# charlie.net
KiCad netlist of a schematic drawn in EAGLE
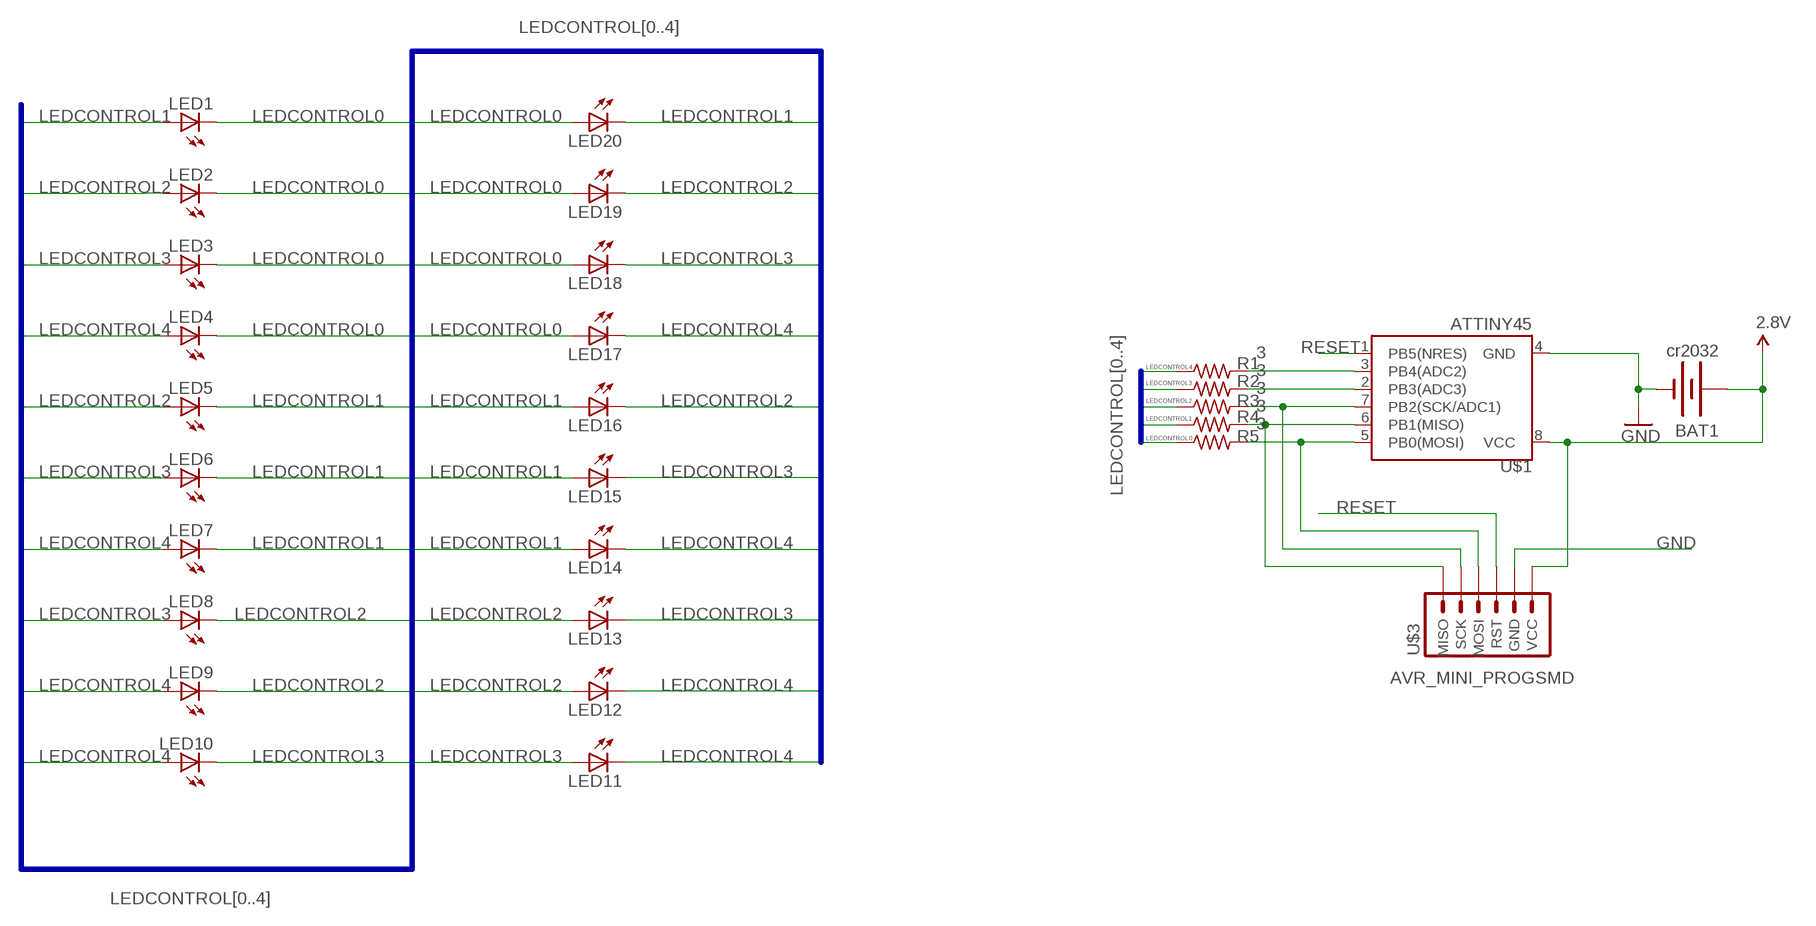
[diagram p0: schematic, sheet 1]

(export (version "E")
  (design (tool "Eeschema 10.0.6"))
  (components
    (comp (ref "BAT1")
      (value "cr2032")
      (footprint "eagle-import:BATTCON_20MM")
      (libsource (lib "eagle-import") (part "BATTERY20SMD"))
    )
    (comp (ref "LED1")
      (value "LEDCHIP-LED0805")
      (footprint "eagle-import:CHIP-LED0805")
      (libsource (lib "eagle-import") (part "LEDCHIP-LED0805"))
    )
    (comp (ref "LED2")
      (value "LEDCHIP-LED0805")
      (footprint "eagle-import:CHIP-LED0805")
      (libsource (lib "eagle-import") (part "LEDCHIP-LED0805"))
    )
    (comp (ref "LED3")
      (value "LEDCHIP-LED0805")
      (footprint "eagle-import:CHIP-LED0805")
      (libsource (lib "eagle-import") (part "LEDCHIP-LED0805"))
    )
    (comp (ref "LED4")
      (value "LEDCHIP-LED0805")
      (footprint "eagle-import:CHIP-LED0805")
      (libsource (lib "eagle-import") (part "LEDCHIP-LED0805"))
    )
    (comp (ref "LED5")
      (value "LEDCHIP-LED0805")
      (footprint "eagle-import:CHIP-LED0805")
      (libsource (lib "eagle-import") (part "LEDCHIP-LED0805"))
    )
    (comp (ref "LED6")
      (value "LEDCHIP-LED0805")
      (footprint "eagle-import:CHIP-LED0805")
      (libsource (lib "eagle-import") (part "LEDCHIP-LED0805"))
    )
    (comp (ref "LED7")
      (value "LEDCHIP-LED0805")
      (footprint "eagle-import:CHIP-LED0805")
      (libsource (lib "eagle-import") (part "LEDCHIP-LED0805"))
    )
    (comp (ref "LED8")
      (value "LEDCHIP-LED0805")
      (footprint "eagle-import:CHIP-LED0805")
      (libsource (lib "eagle-import") (part "LEDCHIP-LED0805"))
    )
    (comp (ref "LED9")
      (value "LEDCHIP-LED0805")
      (footprint "eagle-import:CHIP-LED0805")
      (libsource (lib "eagle-import") (part "LEDCHIP-LED0805"))
    )
    (comp (ref "LED10")
      (value "LEDCHIP-LED0805")
      (footprint "eagle-import:CHIP-LED0805")
      (libsource (lib "eagle-import") (part "LEDCHIP-LED0805"))
    )
    (comp (ref "LED11")
      (value "LEDCHIP-LED0805")
      (footprint "eagle-import:CHIP-LED0805")
      (libsource (lib "eagle-import") (part "LEDCHIP-LED0805"))
    )
    (comp (ref "LED12")
      (value "LEDCHIP-LED0805")
      (footprint "eagle-import:CHIP-LED0805")
      (libsource (lib "eagle-import") (part "LEDCHIP-LED0805"))
    )
    (comp (ref "LED13")
      (value "LEDCHIP-LED0805")
      (footprint "eagle-import:CHIP-LED0805")
      (libsource (lib "eagle-import") (part "LEDCHIP-LED0805"))
    )
    (comp (ref "LED14")
      (value "LEDCHIP-LED0805")
      (footprint "eagle-import:CHIP-LED0805")
      (libsource (lib "eagle-import") (part "LEDCHIP-LED0805"))
    )
    (comp (ref "LED15")
      (value "LEDCHIP-LED0805")
      (footprint "eagle-import:CHIP-LED0805")
      (libsource (lib "eagle-import") (part "LEDCHIP-LED0805"))
    )
    (comp (ref "LED16")
      (value "LEDCHIP-LED0805")
      (footprint "eagle-import:CHIP-LED0805")
      (libsource (lib "eagle-import") (part "LEDCHIP-LED0805"))
    )
    (comp (ref "LED17")
      (value "LEDCHIP-LED0805")
      (footprint "eagle-import:CHIP-LED0805")
      (libsource (lib "eagle-import") (part "LEDCHIP-LED0805"))
    )
    (comp (ref "LED18")
      (value "LEDCHIP-LED0805")
      (footprint "eagle-import:CHIP-LED0805")
      (libsource (lib "eagle-import") (part "LEDCHIP-LED0805"))
    )
    (comp (ref "LED19")
      (value "LEDCHIP-LED0805")
      (footprint "eagle-import:CHIP-LED0805")
      (libsource (lib "eagle-import") (part "LEDCHIP-LED0805"))
    )
    (comp (ref "LED20")
      (value "LEDCHIP-LED0805")
      (footprint "eagle-import:CHIP-LED0805")
      (libsource (lib "eagle-import") (part "LEDCHIP-LED0805"))
    )
    (comp (ref "R1")
      (value "3")
      (footprint "eagle-import:R0805")
      (libsource (lib "eagle-import") (part "R-US_R0805"))
    )
    (comp (ref "R2")
      (value "3")
      (footprint "eagle-import:R0805")
      (libsource (lib "eagle-import") (part "R-US_R0805"))
    )
    (comp (ref "R3")
      (value "3")
      (footprint "eagle-import:R0805")
      (libsource (lib "eagle-import") (part "R-US_R0805"))
    )
    (comp (ref "R4")
      (value "3")
      (footprint "eagle-import:R0805")
      (libsource (lib "eagle-import") (part "R-US_R0805"))
    )
    (comp (ref "R5")
      (value "3")
      (footprint "eagle-import:R0805")
      (libsource (lib "eagle-import") (part "R-US_R0805"))
    )
    (comp (ref "U$1")
      (value "ATTINY45")
      (footprint "eagle-import:SO08-EIAJ")
      (libsource (lib "eagle-import") (part "ATTINY45"))
    )
    (comp (ref "U$3")
      (value "AVR_MINI_PROGSMD")
      (footprint "eagle-import:AVR_MINI_PROG")
      (libsource (lib "eagle-import") (part "AVR_MINI_PROGSMD"))
    )
  )
  (nets
    (net (code "1") (name "/LEDCONTROL0") (class "Default")
      (node (ref "LED1") (pin "C") (pinfunction "C_C") (pintype "passive"))
      (node (ref "LED17") (pin "A") (pinfunction "A_A") (pintype "passive"))
      (node (ref "LED18") (pin "A") (pinfunction "A_A") (pintype "passive"))
      (node (ref "LED19") (pin "A") (pinfunction "A_A") (pintype "passive"))
      (node (ref "LED2") (pin "C") (pinfunction "C_C") (pintype "passive"))
      (node (ref "LED20") (pin "A") (pinfunction "A_A") (pintype "passive"))
      (node (ref "LED3") (pin "C") (pinfunction "C_C") (pintype "passive"))
      (node (ref "LED4") (pin "C") (pinfunction "C_C") (pintype "passive"))
      (node (ref "R5") (pin "1") (pinfunction "1_1") (pintype "passive"))
    )
    (net (code "2") (name "/LEDCONTROL1") (class "Default")
      (node (ref "LED1") (pin "A") (pinfunction "A_A") (pintype "passive"))
      (node (ref "LED14") (pin "A") (pinfunction "A_A") (pintype "passive"))
      (node (ref "LED15") (pin "A") (pinfunction "A_A") (pintype "passive"))
      (node (ref "LED16") (pin "A") (pinfunction "A_A") (pintype "passive"))
      (node (ref "LED20") (pin "C") (pinfunction "C_C") (pintype "passive"))
      (node (ref "LED5") (pin "C") (pinfunction "C_C") (pintype "passive"))
      (node (ref "LED6") (pin "C") (pinfunction "C_C") (pintype "passive"))
      (node (ref "LED7") (pin "C") (pinfunction "C_C") (pintype "passive"))
      (node (ref "R4") (pin "1") (pinfunction "1_1") (pintype "passive"))
    )
    (net (code "3") (name "/LEDCONTROL2") (class "Default")
      (node (ref "LED12") (pin "A") (pinfunction "A_A") (pintype "passive"))
      (node (ref "LED13") (pin "A") (pinfunction "A_A") (pintype "passive"))
      (node (ref "LED16") (pin "C") (pinfunction "C_C") (pintype "passive"))
      (node (ref "LED19") (pin "C") (pinfunction "C_C") (pintype "passive"))
      (node (ref "LED2") (pin "A") (pinfunction "A_A") (pintype "passive"))
      (node (ref "LED5") (pin "A") (pinfunction "A_A") (pintype "passive"))
      (node (ref "LED8") (pin "C") (pinfunction "C_C") (pintype "passive"))
      (node (ref "LED9") (pin "C") (pinfunction "C_C") (pintype "passive"))
      (node (ref "R3") (pin "1") (pinfunction "1_1") (pintype "passive"))
    )
    (net (code "4") (name "/LEDCONTROL3") (class "Default")
      (node (ref "LED10") (pin "C") (pinfunction "C_C") (pintype "passive"))
      (node (ref "LED11") (pin "A") (pinfunction "A_A") (pintype "passive"))
      (node (ref "LED13") (pin "C") (pinfunction "C_C") (pintype "passive"))
      (node (ref "LED15") (pin "C") (pinfunction "C_C") (pintype "passive"))
      (node (ref "LED18") (pin "C") (pinfunction "C_C") (pintype "passive"))
      (node (ref "LED3") (pin "A") (pinfunction "A_A") (pintype "passive"))
      (node (ref "LED6") (pin "A") (pinfunction "A_A") (pintype "passive"))
      (node (ref "LED8") (pin "A") (pinfunction "A_A") (pintype "passive"))
      (node (ref "R2") (pin "1") (pinfunction "1_1") (pintype "passive"))
    )
    (net (code "5") (name "/LEDCONTROL4") (class "Default")
      (node (ref "LED10") (pin "A") (pinfunction "A_A") (pintype "passive"))
      (node (ref "LED11") (pin "C") (pinfunction "C_C") (pintype "passive"))
      (node (ref "LED12") (pin "C") (pinfunction "C_C") (pintype "passive"))
      (node (ref "LED14") (pin "C") (pinfunction "C_C") (pintype "passive"))
      (node (ref "LED17") (pin "C") (pinfunction "C_C") (pintype "passive"))
      (node (ref "LED4") (pin "A") (pinfunction "A_A") (pintype "passive"))
      (node (ref "LED7") (pin "A") (pinfunction "A_A") (pintype "passive"))
      (node (ref "LED9") (pin "A") (pinfunction "A_A") (pintype "passive"))
      (node (ref "R1") (pin "1") (pinfunction "1_1") (pintype "passive"))
    )
    (net (code "7") (name "/RESET") (class "Default")
      (node (ref "U$1") (pin "1") (pinfunction "PB5(NRES)_1") (pintype "bidirectional"))
      (node (ref "U$3") (pin "3") (pinfunction "RST_3") (pintype "passive"))
    )
    (net (code "8") (name "2.8V") (class "Default")
      (node (ref "BAT1") (pin "1") (pinfunction "+_1") (pintype "power_in"))
      (node (ref "U$1") (pin "8") (pinfunction "VCC_8") (pintype "bidirectional"))
      (node (ref "U$3") (pin "1") (pinfunction "VCC_1") (pintype "passive"))
    )
    (net (code "9") (name "GND") (class "Default")
      (node (ref "BAT1") (pin "2") (pinfunction "-_2") (pintype "power_in"))
      (node (ref "U$1") (pin "4") (pinfunction "GND_4") (pintype "bidirectional"))
      (node (ref "U$3") (pin "2") (pinfunction "GND_2") (pintype "passive"))
    )
    (net (code "10") (name "Net-(U$1-PB0(MOSI))") (class "Default")
      (node (ref "R5") (pin "2") (pinfunction "2_2") (pintype "passive"))
      (node (ref "U$1") (pin "5") (pinfunction "PB0(MOSI)_5") (pintype "bidirectional"))
      (node (ref "U$3") (pin "4") (pinfunction "MOSI_4") (pintype "passive"))
    )
    (net (code "11") (name "Net-(U$1-PB1(MISO))") (class "Default")
      (node (ref "R4") (pin "2") (pinfunction "2_2") (pintype "passive"))
      (node (ref "U$1") (pin "6") (pinfunction "PB1(MISO)_6") (pintype "bidirectional"))
      (node (ref "U$3") (pin "6") (pinfunction "MISO_6") (pintype "passive"))
    )
    (net (code "12") (name "Net-(U$1-PB2(SCK{slash}ADC1))") (class "Default")
      (node (ref "R3") (pin "2") (pinfunction "2_2") (pintype "passive"))
      (node (ref "U$1") (pin "7") (pinfunction "PB2(SCK/ADC1)_7") (pintype "bidirectional"))
      (node (ref "U$3") (pin "5") (pinfunction "SCK_5") (pintype "passive"))
    )
    (net (code "13") (name "Net-(U$1-PB3(ADC3))") (class "Default")
      (node (ref "R2") (pin "2") (pinfunction "2_2") (pintype "passive"))
      (node (ref "U$1") (pin "2") (pinfunction "PB3(ADC3)_2") (pintype "bidirectional"))
    )
    (net (code "14") (name "Net-(U$1-PB4(ADC2))") (class "Default")
      (node (ref "R1") (pin "2") (pinfunction "2_2") (pintype "passive"))
      (node (ref "U$1") (pin "3") (pinfunction "PB4(ADC2)_3") (pintype "bidirectional"))
    )
  )
)
